# SCH_AIME_CARD_READER.net
KiCad netlist of a schematic drawn in EasyEDA
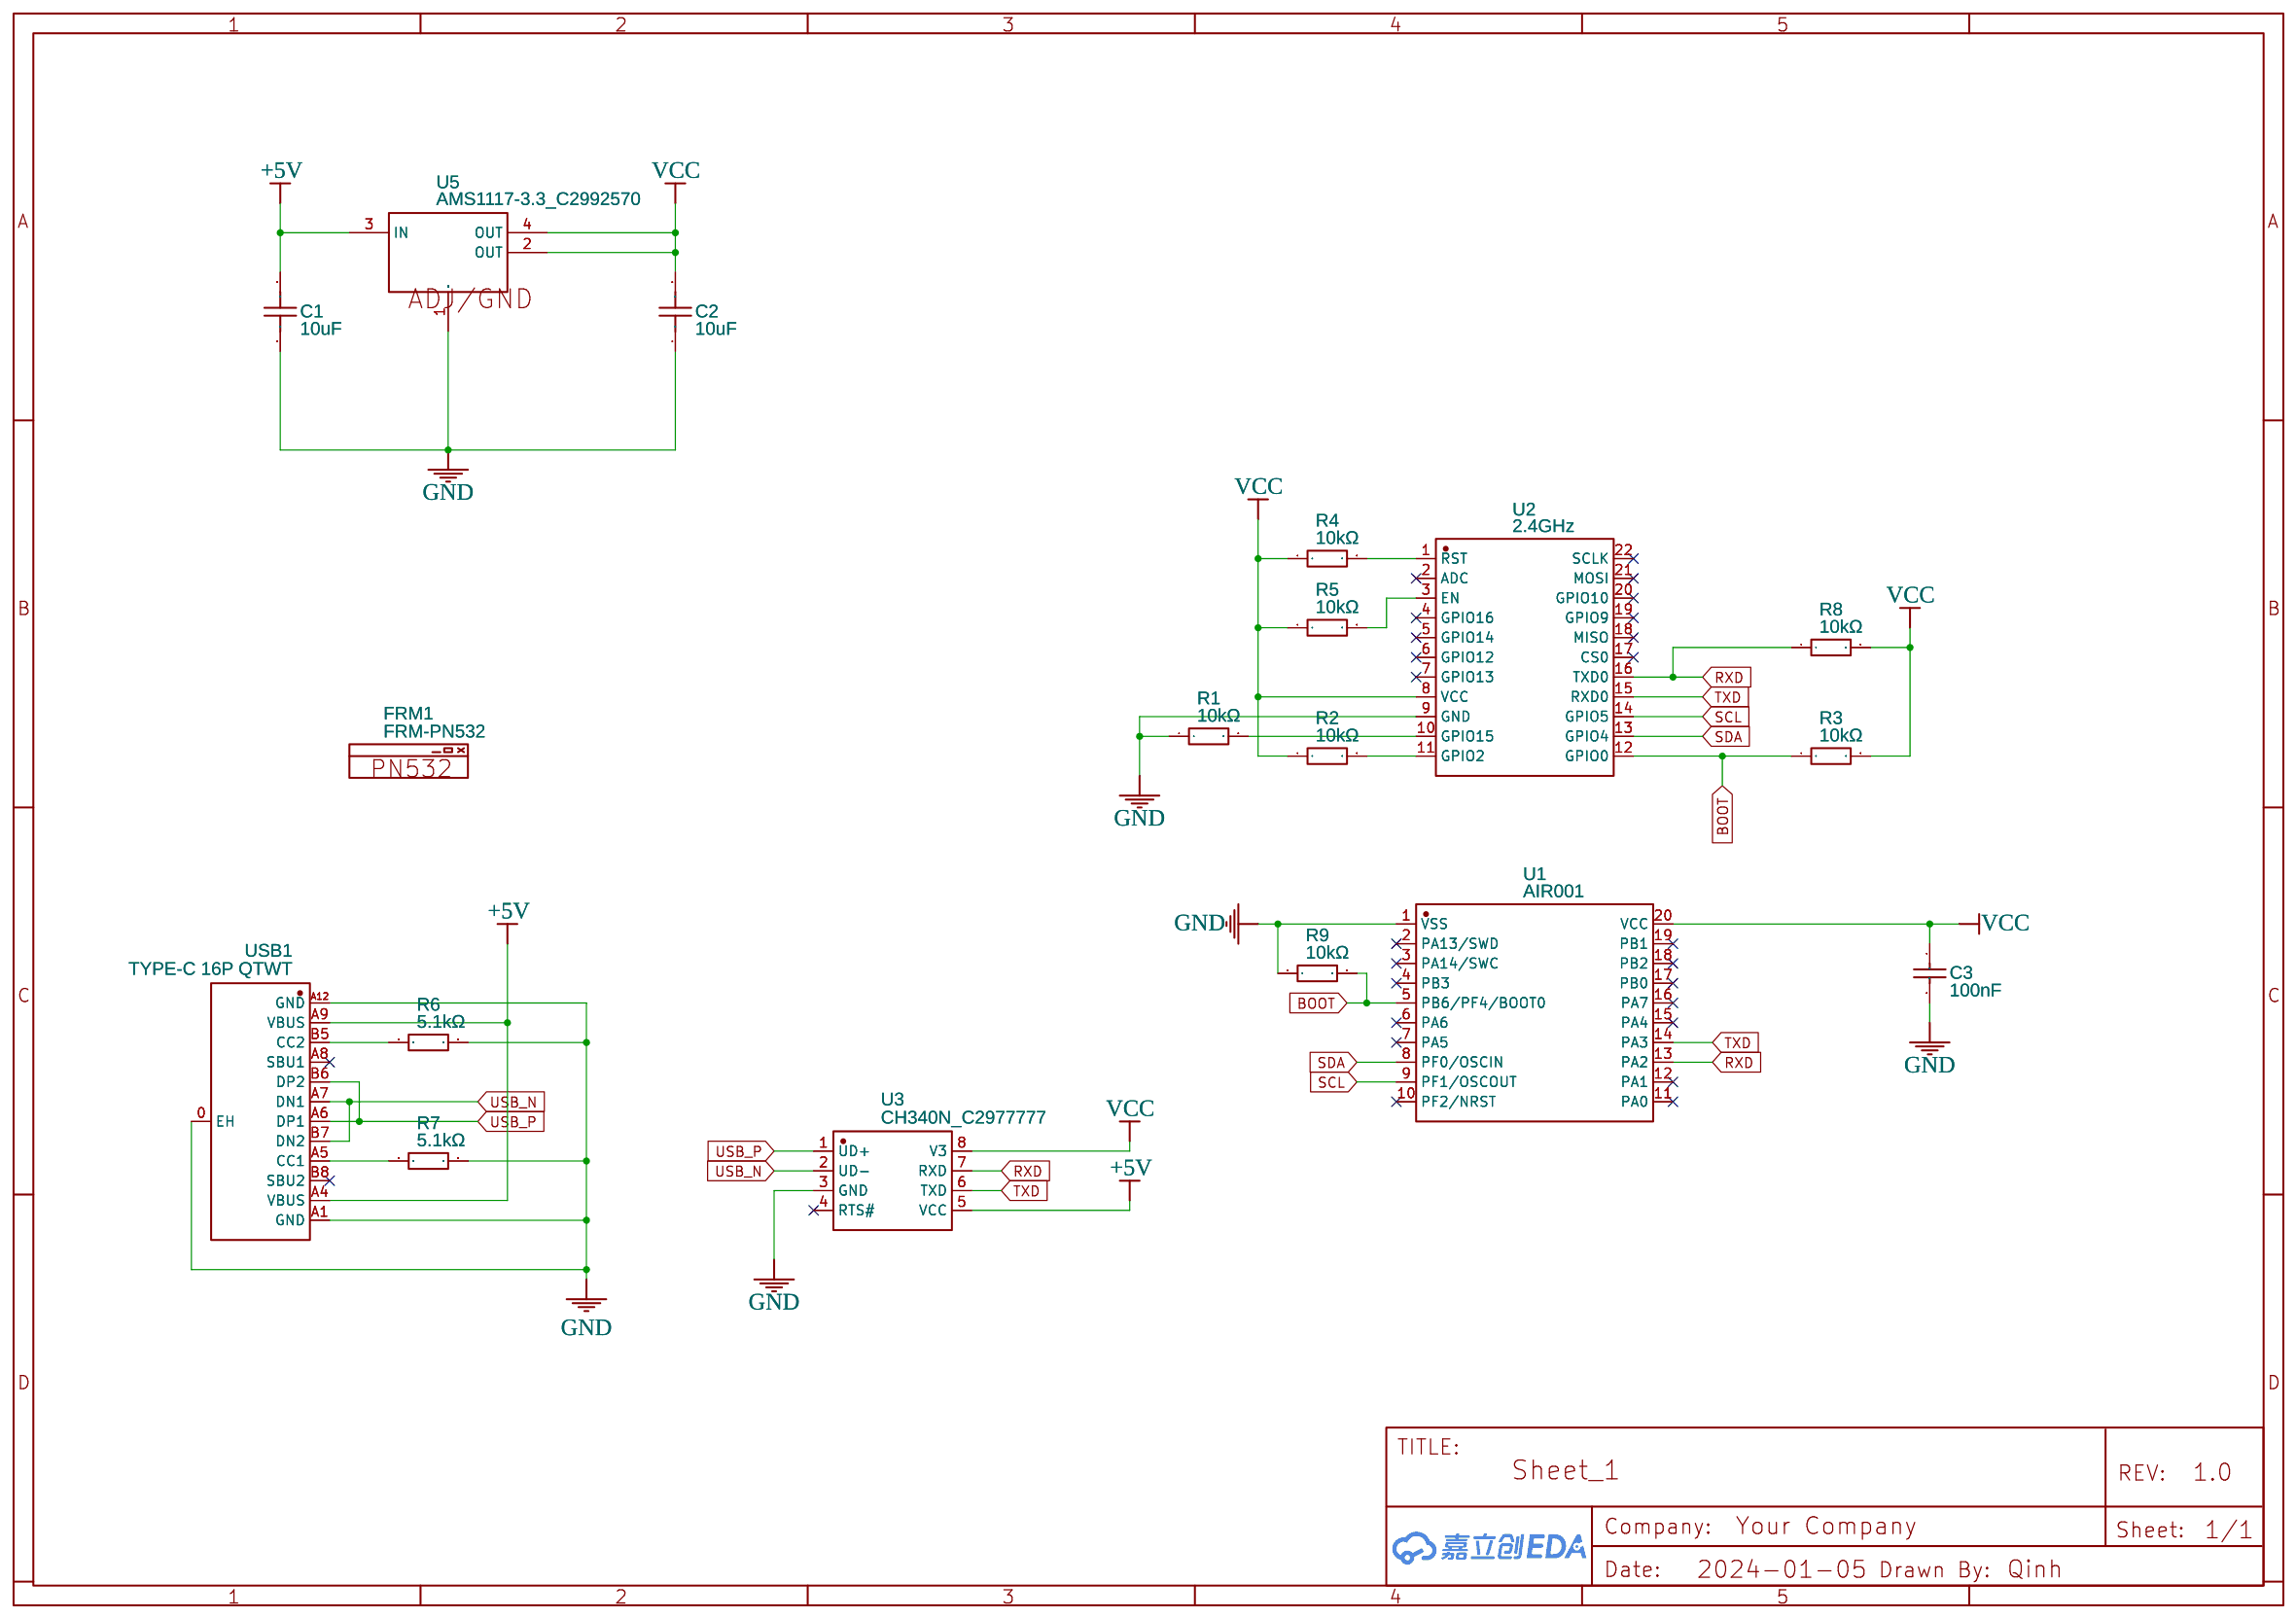
[diagram p0: schematic sheet]

(export (version "E")
  (design (tool "Eeschema 10.0.6"))
  (components
    (comp (ref "C1")
      (value "10uF")
      (fields
        (field (name "Manufacturer Part") "CL10A106KP8NNNC")
        (field (name "Manufacturer") "SAMSUNG(三星)")
      )
      (libsource (lib "") (part "CL10A106KP8NNNC"))
    )
    (comp (ref "C2")
      (value "10uF")
      (fields
        (field (name "Manufacturer Part") "CL10A106KP8NNNC")
        (field (name "Manufacturer") "SAMSUNG(三星)")
      )
      (libsource (lib "") (part "CL10A106KP8NNNC"))
    )
    (comp (ref "C3")
      (value "100nF")
      (fields (field (name "Manufacturer Part") "0603B104K500NT") (field (name "Manufacturer") "FH(风华)"))
      (libsource (lib "") (part "0603B104K500NT"))
    )
    (comp (ref "FRM1") (value "FRM-PN532") (libsource (lib "") (part "FRM-PN532")))
    (comp (ref "R1")
      (value "10kΩ")
      (fields
        (field (name "Manufacturer Part") "0603WAF1002T5E")
        (field (name "Manufacturer") "UNI-ROYAL(厚声)")
      )
      (libsource (lib "") (part "0603WAF1002T5E"))
    )
    (comp (ref "R2")
      (value "10kΩ")
      (fields
        (field (name "Manufacturer Part") "0603WAF1002T5E")
        (field (name "Manufacturer") "UNI-ROYAL(厚声)")
      )
      (libsource (lib "") (part "0603WAF1002T5E"))
    )
    (comp (ref "R3")
      (value "10kΩ")
      (fields
        (field (name "Manufacturer Part") "0603WAF1002T5E")
        (field (name "Manufacturer") "UNI-ROYAL(厚声)")
      )
      (libsource (lib "") (part "0603WAF1002T5E"))
    )
    (comp (ref "R4")
      (value "10kΩ")
      (fields
        (field (name "Manufacturer Part") "0603WAF1002T5E")
        (field (name "Manufacturer") "UNI-ROYAL(厚声)")
      )
      (libsource (lib "") (part "0603WAF1002T5E"))
    )
    (comp (ref "R5")
      (value "10kΩ")
      (fields
        (field (name "Manufacturer Part") "0603WAF1002T5E")
        (field (name "Manufacturer") "UNI-ROYAL(厚声)")
      )
      (libsource (lib "") (part "0603WAF1002T5E"))
    )
    (comp (ref "R6")
      (value "5.1kΩ")
      (fields
        (field (name "BOM_Manufacturer Part") "RMC06035.1K1%N")
        (field (name "BOM_Supplier Part") "C269716")
      )
      (libsource (lib "") (part "RMC06035.1K1%N"))
    )
    (comp (ref "R7")
      (value "5.1kΩ")
      (fields
        (field (name "BOM_Manufacturer Part") "RMC06035.1K1%N")
        (field (name "BOM_Supplier Part") "C269716")
      )
      (libsource (lib "") (part "RMC06035.1K1%N"))
    )
    (comp (ref "R8")
      (value "10kΩ")
      (fields
        (field (name "Manufacturer Part") "0603WAF1002T5E")
        (field (name "Manufacturer") "UNI-ROYAL(厚声)")
      )
      (libsource (lib "") (part "0603WAF1002T5E"))
    )
    (comp (ref "R9")
      (value "10kΩ")
      (fields
        (field (name "Manufacturer Part") "0603WAF1002T5E")
        (field (name "Manufacturer") "UNI-ROYAL(厚声)")
      )
      (libsource (lib "") (part "0603WAF1002T5E"))
    )
    (comp (ref "U1")
      (value "AIR001")
      (fields (field (name "Manufacturer") "Luat(合宙)"))
      (libsource (lib "") (part "AIR001"))
    )
    (comp (ref "U2")
      (value "2.4GHz")
      (fields
        (field (name "Manufacturer Part") "ESP-12F(ESP8266MOD)")
        (field (name "Manufacturer") "Ai-Thinker(安信可)")
      )
      (libsource (lib "") (part "ESP-12F(ESP8266MOD)"))
    )
    (comp (ref "U3")
      (value "CH340N_C2977777")
      (fields (field (name "BOM_Manufacturer Part") "CH340N") (field (name "BOM_Supplier Part") "C2977777"))
      (libsource (lib "") (part "CH340N_C2977777"))
    )
    (comp (ref "U5")
      (value "AMS1117-3.3_C2992570")
      (fields
        (field (name "BOM_Manufacturer Part") "AMS1117-3.3")
        (field (name "BOM_Supplier Part") "C2992570")
      )
      (libsource (lib "") (part "AMS1117-3.3_C2992570"))
    )
    (comp (ref "USB1")
      (value "TYPE-C 16P QTWT")
      (fields (field (name "Manufacturer") "SHOU HAN(首韩)"))
      (libsource (lib "") (part "TYPE-C 16P QTWT"))
    )
  )
  (nets
    (net (code "1") (name "+5V") (class "Default")
      (node (ref "C1") (pin "2") (pinfunction "2_2") (pintype "unspecified"))
      (node (ref "U3") (pin "5") (pinfunction "VCC_5") (pintype "unspecified"))
      (node (ref "U5") (pin "3") (pinfunction "IN_3") (pintype "passive"))
      (node (ref "USB1") (pin "A4") (pinfunction "VBUS_A4") (pintype "unspecified"))
      (node (ref "USB1") (pin "A9") (pinfunction "VBUS_A9") (pintype "unspecified"))
    )
    (net (code "2") (name "BOOT") (class "Default")
      (node (ref "R3") (pin "1") (pinfunction "1_1") (pintype "input"))
      (node (ref "R9") (pin "2") (pinfunction "2_2") (pintype "input"))
      (node (ref "U1") (pin "5") (pinfunction "PB6/PF4/BOOT0_5") (pintype "unspecified"))
      (node (ref "U2") (pin "12") (pinfunction "GPIO0_12") (pintype "unspecified"))
    )
    (net (code "3") (name "GND") (class "Default")
      (node (ref "C1") (pin "1") (pinfunction "1_1") (pintype "unspecified"))
      (node (ref "C2") (pin "1") (pinfunction "1_1") (pintype "unspecified"))
      (node (ref "C3") (pin "2") (pinfunction "2_2") (pintype "input"))
      (node (ref "R1") (pin "1") (pinfunction "1_1") (pintype "input"))
      (node (ref "R6") (pin "1") (pinfunction "1_1") (pintype "unspecified"))
      (node (ref "R7") (pin "1") (pinfunction "1_1") (pintype "unspecified"))
      (node (ref "R9") (pin "1") (pinfunction "1_1") (pintype "input"))
      (node (ref "U1") (pin "1") (pinfunction "VSS_1") (pintype "unspecified"))
      (node (ref "U2") (pin "9") (pinfunction "GND_9") (pintype "unspecified"))
      (node (ref "U3") (pin "3") (pinfunction "GND_3") (pintype "unspecified"))
      (node (ref "U5") (pin "1") (pinfunction "ADJ/GND_1") (pintype "passive"))
      (node (ref "USB1") (pin "0") (pinfunction "EH_0") (pintype "unspecified"))
      (node (ref "USB1") (pin "A1") (pinfunction "GND_A1") (pintype "unspecified"))
      (node (ref "USB1") (pin "A12") (pinfunction "GND_A12") (pintype "unspecified"))
    )
    (net (code "4") (name "Net-(U2-EN)") (class "Default")
      (node (ref "R5") (pin "2") (pinfunction "2_2") (pintype "input"))
      (node (ref "U2") (pin "3") (pinfunction "EN_3") (pintype "unspecified"))
    )
    (net (code "5") (name "Net-(U2-GPIO2)") (class "Default")
      (node (ref "R2") (pin "2") (pinfunction "2_2") (pintype "input"))
      (node (ref "U2") (pin "11") (pinfunction "GPIO2_11") (pintype "unspecified"))
    )
    (net (code "6") (name "Net-(U2-GPIO15)") (class "Default")
      (node (ref "R1") (pin "2") (pinfunction "2_2") (pintype "input"))
      (node (ref "U2") (pin "10") (pinfunction "GPIO15_10") (pintype "unspecified"))
    )
    (net (code "7") (name "Net-(U2-RST)") (class "Default")
      (node (ref "R4") (pin "2") (pinfunction "2_2") (pintype "input"))
      (node (ref "U2") (pin "1") (pinfunction "RST_1") (pintype "unspecified"))
    )
    (net (code "8") (name "Net-(USB1-CC1)") (class "Default")
      (node (ref "R7") (pin "2") (pinfunction "2_2") (pintype "unspecified"))
      (node (ref "USB1") (pin "A5") (pinfunction "CC1_A5") (pintype "unspecified"))
    )
    (net (code "9") (name "Net-(USB1-CC2)") (class "Default")
      (node (ref "R6") (pin "2") (pinfunction "2_2") (pintype "unspecified"))
      (node (ref "USB1") (pin "B5") (pinfunction "CC2_B5") (pintype "unspecified"))
    )
    (net (code "10") (name "RXD") (class "Default")
      (node (ref "R8") (pin "1") (pinfunction "1_1") (pintype "input"))
      (node (ref "U1") (pin "13") (pinfunction "PA2_13") (pintype "unspecified"))
      (node (ref "U2") (pin "16") (pinfunction "TXD0_16") (pintype "unspecified"))
      (node (ref "U3") (pin "7") (pinfunction "RXD_7") (pintype "unspecified"))
    )
    (net (code "11") (name "SCL") (class "Default")
      (node (ref "U1") (pin "9") (pinfunction "PF1/OSCOUT_9") (pintype "unspecified"))
      (node (ref "U2") (pin "14") (pinfunction "GPIO5_14") (pintype "unspecified"))
    )
    (net (code "12") (name "SDA") (class "Default")
      (node (ref "U1") (pin "8") (pinfunction "PF0/OSCIN_8") (pintype "unspecified"))
      (node (ref "U2") (pin "13") (pinfunction "GPIO4_13") (pintype "unspecified"))
    )
    (net (code "13") (name "TXD") (class "Default")
      (node (ref "U1") (pin "14") (pinfunction "PA3_14") (pintype "unspecified"))
      (node (ref "U2") (pin "15") (pinfunction "RXD0_15") (pintype "unspecified"))
      (node (ref "U3") (pin "6") (pinfunction "TXD_6") (pintype "unspecified"))
    )
    (net (code "14") (name "USB_N") (class "Default")
      (node (ref "U3") (pin "2") (pinfunction "UD-_2") (pintype "unspecified"))
      (node (ref "USB1") (pin "A7") (pinfunction "DN1_A7") (pintype "unspecified"))
      (node (ref "USB1") (pin "B7") (pinfunction "DN2_B7") (pintype "unspecified"))
    )
    (net (code "15") (name "USB_P") (class "Default")
      (node (ref "U3") (pin "1") (pinfunction "UD+_1") (pintype "unspecified"))
      (node (ref "USB1") (pin "A6") (pinfunction "DP1_A6") (pintype "unspecified"))
      (node (ref "USB1") (pin "B6") (pinfunction "DP2_B6") (pintype "unspecified"))
    )
    (net (code "16") (name "VCC") (class "Default")
      (node (ref "C2") (pin "2") (pinfunction "2_2") (pintype "unspecified"))
      (node (ref "C3") (pin "1") (pinfunction "1_1") (pintype "input"))
      (node (ref "R2") (pin "1") (pinfunction "1_1") (pintype "input"))
      (node (ref "R3") (pin "2") (pinfunction "2_2") (pintype "input"))
      (node (ref "R4") (pin "1") (pinfunction "1_1") (pintype "input"))
      (node (ref "R5") (pin "1") (pinfunction "1_1") (pintype "input"))
      (node (ref "R8") (pin "2") (pinfunction "2_2") (pintype "input"))
      (node (ref "U1") (pin "20") (pinfunction "VCC_20") (pintype "unspecified"))
      (node (ref "U2") (pin "8") (pinfunction "VCC_8") (pintype "unspecified"))
      (node (ref "U3") (pin "8") (pinfunction "V3_8") (pintype "unspecified"))
      (node (ref "U5") (pin "2") (pinfunction "OUT_2") (pintype "passive"))
      (node (ref "U5") (pin "4") (pinfunction "OUT_4") (pintype "passive"))
    )
    (net (code "17") (name "unconnected-(U1-PA0-Pad11)") (class "Default")
      (node (ref "U1") (pin "11") (pinfunction "PA0_11") (pintype "unspecified+no_connect"))
    )
    (net (code "18") (name "unconnected-(U1-PA1-Pad12)") (class "Default")
      (node (ref "U1") (pin "12") (pinfunction "PA1_12") (pintype "unspecified+no_connect"))
    )
    (net (code "19") (name "unconnected-(U1-PA4-Pad15)") (class "Default")
      (node (ref "U1") (pin "15") (pinfunction "PA4_15") (pintype "unspecified+no_connect"))
    )
    (net (code "20") (name "unconnected-(U1-PA5-Pad7)") (class "Default")
      (node (ref "U1") (pin "7") (pinfunction "PA5_7") (pintype "unspecified+no_connect"))
    )
    (net (code "21") (name "unconnected-(U1-PA6-Pad6)") (class "Default")
      (node (ref "U1") (pin "6") (pinfunction "PA6_6") (pintype "unspecified+no_connect"))
    )
    (net (code "22") (name "unconnected-(U1-PA7-Pad16)") (class "Default")
      (node (ref "U1") (pin "16") (pinfunction "PA7_16") (pintype "unspecified+no_connect"))
    )
    (net (code "23") (name "unconnected-(U1-PA13{slash}SWD-Pad2)") (class "Default")
      (node (ref "U1") (pin "2") (pinfunction "PA13/SWD_2") (pintype "unspecified+no_connect"))
    )
    (net (code "24") (name "unconnected-(U1-PA14{slash}SWC-Pad3)") (class "Default")
      (node (ref "U1") (pin "3") (pinfunction "PA14/SWC_3") (pintype "unspecified+no_connect"))
    )
    (net (code "25") (name "unconnected-(U1-PB0-Pad17)") (class "Default")
      (node (ref "U1") (pin "17") (pinfunction "PB0_17") (pintype "unspecified+no_connect"))
    )
    (net (code "26") (name "unconnected-(U1-PB1-Pad19)") (class "Default")
      (node (ref "U1") (pin "19") (pinfunction "PB1_19") (pintype "unspecified+no_connect"))
    )
    (net (code "27") (name "unconnected-(U1-PB2-Pad18)") (class "Default")
      (node (ref "U1") (pin "18") (pinfunction "PB2_18") (pintype "unspecified+no_connect"))
    )
    (net (code "28") (name "unconnected-(U1-PB3-Pad4)") (class "Default")
      (node (ref "U1") (pin "4") (pinfunction "PB3_4") (pintype "unspecified+no_connect"))
    )
    (net (code "29") (name "unconnected-(U1-PF2{slash}NRST-Pad10)") (class "Default")
      (node (ref "U1") (pin "10") (pinfunction "PF2/NRST_10") (pintype "unspecified+no_connect"))
    )
    (net (code "30") (name "unconnected-(U2-ADC-Pad2)") (class "Default")
      (node (ref "U2") (pin "2") (pinfunction "ADC_2") (pintype "unspecified+no_connect"))
    )
    (net (code "31") (name "unconnected-(U2-CS0-Pad17)") (class "Default")
      (node (ref "U2") (pin "17") (pinfunction "CS0_17") (pintype "unspecified+no_connect"))
    )
    (net (code "32") (name "unconnected-(U2-GPIO9-Pad19)") (class "Default")
      (node (ref "U2") (pin "19") (pinfunction "GPIO9_19") (pintype "unspecified+no_connect"))
    )
    (net (code "33") (name "unconnected-(U2-GPIO10-Pad20)") (class "Default")
      (node (ref "U2") (pin "20") (pinfunction "GPIO10_20") (pintype "unspecified+no_connect"))
    )
    (net (code "34") (name "unconnected-(U2-GPIO12-Pad6)") (class "Default")
      (node (ref "U2") (pin "6") (pinfunction "GPIO12_6") (pintype "unspecified+no_connect"))
    )
    (net (code "35") (name "unconnected-(U2-GPIO13-Pad7)") (class "Default")
      (node (ref "U2") (pin "7") (pinfunction "GPIO13_7") (pintype "unspecified+no_connect"))
    )
    (net (code "36") (name "unconnected-(U2-GPIO14-Pad5)") (class "Default")
      (node (ref "U2") (pin "5") (pinfunction "GPIO14_5") (pintype "unspecified+no_connect"))
    )
    (net (code "37") (name "unconnected-(U2-GPIO16-Pad4)") (class "Default")
      (node (ref "U2") (pin "4") (pinfunction "GPIO16_4") (pintype "unspecified+no_connect"))
    )
    (net (code "38") (name "unconnected-(U2-MISO-Pad18)") (class "Default")
      (node (ref "U2") (pin "18") (pinfunction "MISO_18") (pintype "unspecified+no_connect"))
    )
    (net (code "39") (name "unconnected-(U2-MOSI-Pad21)") (class "Default")
      (node (ref "U2") (pin "21") (pinfunction "MOSI_21") (pintype "unspecified+no_connect"))
    )
    (net (code "40") (name "unconnected-(U2-SCLK-Pad22)") (class "Default")
      (node (ref "U2") (pin "22") (pinfunction "SCLK_22") (pintype "unspecified+no_connect"))
    )
    (net (code "41") (name "unconnected-(U3-RTS#-Pad4)") (class "Default")
      (node (ref "U3") (pin "4") (pinfunction "RTS#_4") (pintype "unspecified+no_connect"))
    )
    (net (code "42") (name "unconnected-(USB1-SBU1-PadA8)") (class "Default")
      (node (ref "USB1") (pin "A8") (pinfunction "SBU1_A8") (pintype "unspecified+no_connect"))
    )
    (net (code "43") (name "unconnected-(USB1-SBU2-PadB8)") (class "Default")
      (node (ref "USB1") (pin "B8") (pinfunction "SBU2_B8") (pintype "unspecified+no_connect"))
    )
  )
)
